# Main.net
KiCad netlist of a schematic drawn in Altium Designer
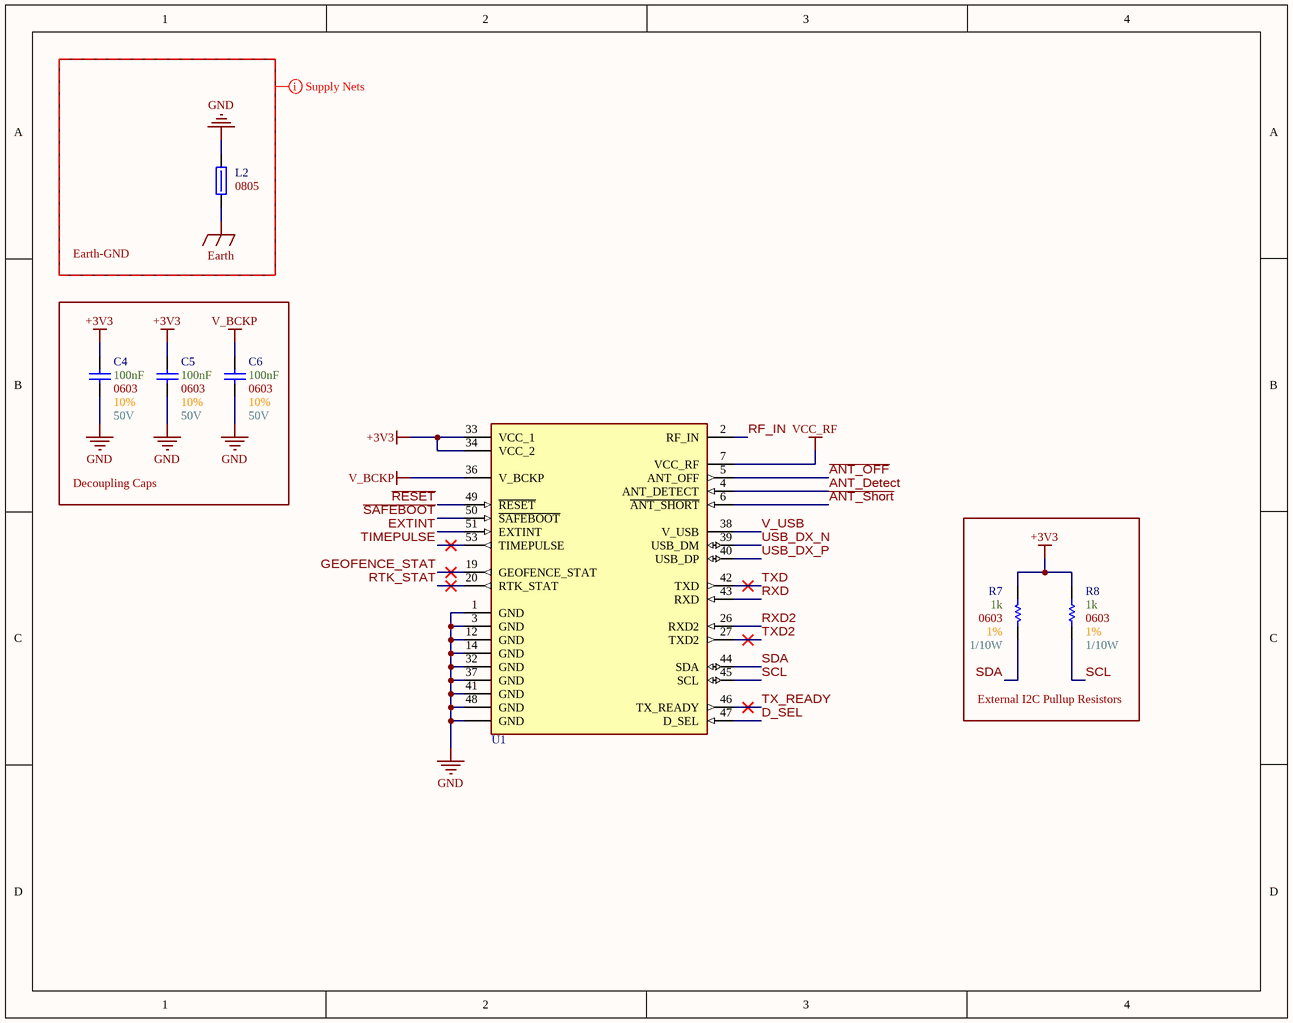
[diagram p0: Main.SchDoc]

(export (version "E")
  (design (tool "Eeschema 10.0.6"))
  (components
    (comp (ref "C4")
      (value "[Cap] 0603 0.1uF 10% 50V")
      (footprint "[Cap] SMD 0603")
      (description "CL10B104KB8NNNC")
      (fields
        (field (name "MAX VOLTAGE") "50V")
        (field (name "SIZE PACKAGE") "0603")
        (field (name "TOLERANCE") "10%")
        (field (name "CAPACITANCE") "100nF")
      )
      (libsource (lib "Capacitors") (part "[Cap] 0603 0.1uF 10% 50V"))
    )
    (comp (ref "C5")
      (value "[Cap] 0603 0.1uF 10% 50V")
      (footprint "[Cap] SMD 0603")
      (description "CL10B104KB8NNNC")
      (fields
        (field (name "MAX VOLTAGE") "50V")
        (field (name "SIZE PACKAGE") "0603")
        (field (name "TOLERANCE") "10%")
        (field (name "CAPACITANCE") "100nF")
      )
      (libsource (lib "Capacitors") (part "[Cap] 0603 0.1uF 10% 50V"))
    )
    (comp (ref "C6")
      (value "[Cap] 0603 0.1uF 10% 50V")
      (footprint "[Cap] SMD 0603")
      (description "CL10B104KB8NNNC")
      (fields
        (field (name "MAX VOLTAGE") "50V")
        (field (name "SIZE PACKAGE") "0603")
        (field (name "TOLERANCE") "10%")
        (field (name "CAPACITANCE") "100nF")
      )
      (libsource (lib "Capacitors") (part "[Cap] 0603 0.1uF 10% 50V"))
    )
    (comp (ref "L2")
      (value "652-MH2029-300Y")
      (footprint "[Ferrite] SMD 0805")
      (fields (field (name "SIZE PACKAGE") "0805"))
      (libsource (lib "Ferrite Beads") (part "[Ferrite] SMD 0805 3A 30ohm"))
    )
    (comp (ref "R7")
      (value "[1k] SMD 0603 1% 1/10W")
      (footprint "[Res] SMD 0603")
      (description "RMCF0603FT1K00")
      (fields
        (field (name "WATTAGE") "1/10W")
        (field (name "TOLERANCE") "1%")
        (field (name "RESISTANCE") "1k")
        (field (name "SIZE PACKAGE") "0603")
      )
      (libsource (lib "Resistors") (part "[1k] SMD 0603 1% 1/10W"))
    )
    (comp (ref "R8")
      (value "[1k] SMD 0603 1% 1/10W")
      (footprint "[Res] SMD 0603")
      (description "RMCF0603FT1K00")
      (fields
        (field (name "WATTAGE") "1/10W")
        (field (name "TOLERANCE") "1%")
        (field (name "RESISTANCE") "1k")
        (field (name "SIZE PACKAGE") "0603")
      )
      (libsource (lib "Resistors") (part "[1k] SMD 0603 1% 1/10W"))
    )
    (comp (ref "U1")
      (value "High-Precision Triple Band GNSS Module")
      (footprint "[GNSS] ZED-F20P-00B")
      (description "ZED-F20P-00B")
      (libsource (lib "ICs") (part "[GNSS] ZED-F20P-00B"))
    )
  )
  (nets
    (net (code "1") (name "+3V3") (class "Default")
      (node (ref "C4") (pin "2") (pinfunction "2_2") (pintype "passive"))
      (node (ref "C5") (pin "2") (pinfunction "2_2") (pintype "passive"))
      (node (ref "R7") (pin "2") (pinfunction "2_2") (pintype "passive"))
      (node (ref "R8") (pin "2") (pinfunction "2_2") (pintype "passive"))
      (node (ref "U1") (pin "33") (pinfunction "VCC_1_33") (pintype "power_in"))
      (node (ref "U1") (pin "34") (pinfunction "VCC_2_34") (pintype "power_in"))
    )
    (net (code "2") (name "/ANT_Detect") (class "Default")
      (node (ref "U1") (pin "4") (pinfunction "ANT_DETECT_4") (pintype "input"))
    )
    (net (code "3") (name "/ANT_OFF") (class "Default")
      (node (ref "U1") (pin "5") (pinfunction "ANT_OFF_5") (pintype "output"))
    )
    (net (code "4") (name "/ANT_Short") (class "Default")
      (node (ref "U1") (pin "6") (pinfunction "ANT_SHORT_6") (pintype "input"))
    )
    (net (code "5") (name "/D_SEL") (class "Default")
      (node (ref "U1") (pin "47") (pinfunction "D_SEL_47") (pintype "input"))
    )
    (net (code "6") (name "/EXTINT") (class "Default")
      (node (ref "U1") (pin "51") (pinfunction "EXTINT_51") (pintype "input"))
    )
    (net (code "7") (name "/GEOFENCE_STAT") (class "Default")
      (node (ref "U1") (pin "19") (pinfunction "GEOFENCE_STAT_19") (pintype "output"))
    )
    (net (code "8") (name "/RESET") (class "Default")
      (node (ref "U1") (pin "49") (pinfunction "RESET_49") (pintype "input"))
    )
    (net (code "9") (name "/RF_IN") (class "Default")
      (node (ref "U1") (pin "2") (pinfunction "RF_IN_2") (pintype "passive"))
    )
    (net (code "10") (name "/RTK_STAT") (class "Default")
      (node (ref "U1") (pin "20") (pinfunction "RTK_STAT_20") (pintype "output"))
    )
    (net (code "11") (name "/RXD") (class "Default")
      (node (ref "U1") (pin "43") (pinfunction "RXD_43") (pintype "input"))
    )
    (net (code "12") (name "/RXD2") (class "Default")
      (node (ref "U1") (pin "26") (pinfunction "RXD2_26") (pintype "input"))
    )
    (net (code "13") (name "/SAFEBOOT") (class "Default")
      (node (ref "U1") (pin "50") (pinfunction "SAFEBOOT_50") (pintype "input"))
    )
    (net (code "14") (name "/SCL") (class "Default")
      (node (ref "R8") (pin "1") (pinfunction "1_1") (pintype "passive"))
      (node (ref "U1") (pin "45") (pinfunction "SCL_45") (pintype "bidirectional"))
    )
    (net (code "15") (name "/SDA") (class "Default")
      (node (ref "R7") (pin "1") (pinfunction "1_1") (pintype "passive"))
      (node (ref "U1") (pin "44") (pinfunction "SDA_44") (pintype "bidirectional"))
    )
    (net (code "16") (name "/TIMEPULSE") (class "Default")
      (node (ref "U1") (pin "53") (pinfunction "TIMEPULSE_53") (pintype "output"))
    )
    (net (code "17") (name "/TXD") (class "Default")
      (node (ref "U1") (pin "42") (pinfunction "TXD_42") (pintype "output"))
    )
    (net (code "18") (name "/TXD2") (class "Default")
      (node (ref "U1") (pin "27") (pinfunction "TXD2_27") (pintype "output"))
    )
    (net (code "19") (name "/TX_READY") (class "Default")
      (node (ref "U1") (pin "46") (pinfunction "TX_READY_46") (pintype "output"))
    )
    (net (code "20") (name "/USB_DX_N") (class "Default")
      (node (ref "U1") (pin "39") (pinfunction "USB_DM_39") (pintype "bidirectional"))
    )
    (net (code "21") (name "/USB_DX_P") (class "Default")
      (node (ref "U1") (pin "40") (pinfunction "USB_DP_40") (pintype "bidirectional"))
    )
    (net (code "22") (name "/V_USB") (class "Default")
      (node (ref "U1") (pin "38") (pinfunction "V_USB_38") (pintype "power_in"))
    )
    (net (code "23") (name "Earth") (class "Default")
      (node (ref "L2") (pin "1") (pinfunction "1_1") (pintype "passive"))
    )
    (net (code "24") (name "GND") (class "Default")
      (node (ref "C4") (pin "1") (pinfunction "1_1") (pintype "passive"))
      (node (ref "C5") (pin "1") (pinfunction "1_1") (pintype "passive"))
      (node (ref "C6") (pin "1") (pinfunction "1_1") (pintype "passive"))
      (node (ref "L2") (pin "2") (pinfunction "2_2") (pintype "passive"))
      (node (ref "U1") (pin "1") (pinfunction "GND_1") (pintype "power_in"))
      (node (ref "U1") (pin "12") (pinfunction "GND_12") (pintype "power_in"))
      (node (ref "U1") (pin "14") (pinfunction "GND_14") (pintype "power_in"))
      (node (ref "U1") (pin "3") (pinfunction "GND_3") (pintype "power_in"))
      (node (ref "U1") (pin "32") (pinfunction "GND_32") (pintype "power_in"))
      (node (ref "U1") (pin "37") (pinfunction "GND_37") (pintype "power_in"))
      (node (ref "U1") (pin "41") (pinfunction "GND_41") (pintype "power_in"))
      (node (ref "U1") (pin "48") (pinfunction "GND_48") (pintype "power_in"))
      (node (ref "U1") (pin "GND") (pinfunction "GND_GND") (pintype "power_in"))
    )
    (net (code "25") (name "VCC_RF") (class "Default")
      (node (ref "U1") (pin "7") (pinfunction "VCC_RF_7") (pintype "power_in"))
    )
    (net (code "26") (name "V_BCKP") (class "Default")
      (node (ref "C6") (pin "2") (pinfunction "2_2") (pintype "passive"))
      (node (ref "U1") (pin "36") (pinfunction "V_BCKP_36") (pintype "power_in"))
    )
  )
)
